# SCHEM_MOTEUR_PDB_OFA.net
KiCad netlist of a schematic drawn in Altium Designer
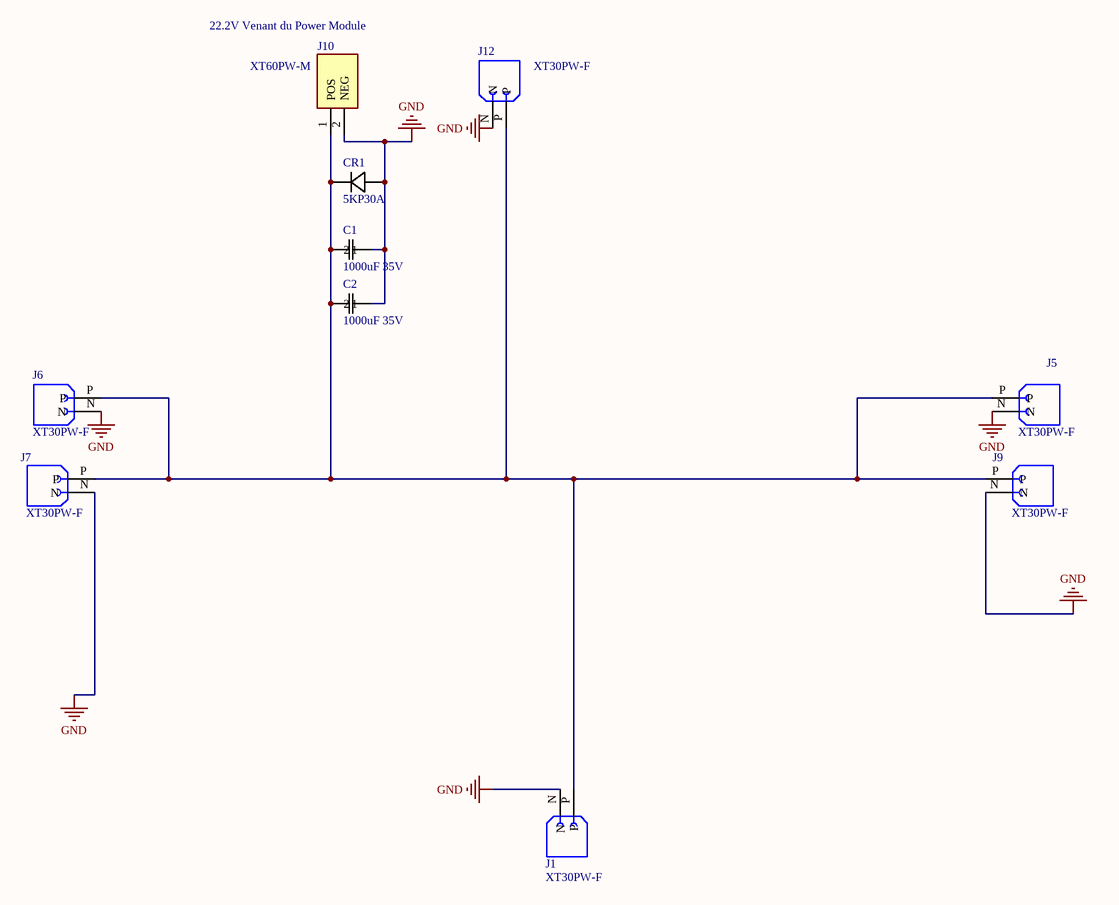
[diagram p0: SCHEM_MOTEUR_PDB_OFA.SchDoc]

(export (version "E")
  (design (tool "Eeschema 10.0.6"))
  (components
    (comp (ref "C1")
      (value "1000uF 35V")
      (footprint "CAP_RX_12P5X25_RUB")
      (fields
        (field (name "MANUFACTURER_PART_NUMBER") "35RX301000M12.5X25")
        (field (name "COPYRIGHT") "Copyright (C) 2026 Ultra Librarian. All rights reserved.")
      )
      (libsource (lib "Symbol_library") (part "35RX301000M12.5X25"))
    )
    (comp (ref "C2")
      (value "1000uF 35V")
      (footprint "CAP_RX_12P5X25_RUB")
      (fields
        (field (name "MANUFACTURER_PART_NUMBER") "35RX301000M12.5X25")
        (field (name "COPYRIGHT") "Copyright (C) 2026 Ultra Librarian. All rights reserved.")
      )
      (libsource (lib "Symbol_library") (part "35RX301000M12.5X25"))
    )
    (comp (ref "CR1")
      (value "5KP30A")
      (footprint "DIODE_P600_VIS")
      (description "Description")
      (fields (field (name "COPYRIGHT") "Copyright (C) 2026 Ultra Librarian. All rights reserved."))
      (libsource (lib "Symbol_library") (part "5KP30A"))
    )
    (comp (ref "J1")
      (value "XT30PW-F")
      (footprint "AMASS_XT30PW-F")
      (description "Socket; DC supply; XT30; female; PIN: 2; on PCBs; THT; yellow; 15A")
      (fields (field (name "MF") "amass"))
      (libsource (lib "Symbol_library") (part "XT30PW-F"))
    )
    (comp (ref "J5")
      (value "XT30PW-F")
      (footprint "AMASS_XT30PW-F")
      (description "Socket; DC supply; XT30; female; PIN: 2; on PCBs; THT; yellow; 15A")
      (fields (field (name "MF") "amass"))
      (libsource (lib "Symbol_library") (part "XT30PW-F"))
    )
    (comp (ref "J6")
      (value "XT30PW-F")
      (footprint "AMASS_XT30PW-F")
      (description "Socket; DC supply; XT30; female; PIN: 2; on PCBs; THT; yellow; 15A")
      (fields (field (name "MF") "amass"))
      (libsource (lib "") (part "XT30PW-F_1"))
    )
    (comp (ref "J7")
      (value "XT30PW-F")
      (footprint "AMASS_XT30PW-F")
      (description "Socket; DC supply; XT30; female; PIN: 2; on PCBs; THT; yellow; 15A")
      (fields (field (name "MF") "amass"))
      (libsource (lib "") (part "XT30PW-F_1"))
    )
    (comp (ref "J9")
      (value "XT30PW-F")
      (footprint "AMASS_XT30PW-F")
      (description "Socket; DC supply; XT30; female; PIN: 2; on PCBs; THT; yellow; 15A")
      (fields (field (name "MF") "amass"))
      (libsource (lib "Symbol_library") (part "XT30PW-F"))
    )
    (comp (ref "J10")
      (value "XT60PW-M")
      (footprint "AMASS_XT60PW-M")
      (description "Socket, DC supply, male, PIN: 2")
      (fields (field (name "MF") "AMASS"))
      (libsource (lib "Symbol_library") (part "XT60PW-M"))
    )
    (comp (ref "J12")
      (value "XT30PW-F")
      (footprint "AMASS_XT30PW-F")
      (description "Socket; DC supply; XT30; female; PIN: 2; on PCBs; THT; yellow; 15A")
      (fields (field (name "MF") "amass"))
      (libsource (lib "") (part "XT30PW-F_1"))
    )
  )
  (nets
    (net (code "1") (name "GND") (class "Default")
      (node (ref "C1") (pin "2") (pinfunction "2_2") (pintype "passive"))
      (node (ref "C2") (pin "2") (pinfunction "2_2") (pintype "passive"))
      (node (ref "CR1") (pin "2") (pinfunction "2_2") (pintype "passive"))
      (node (ref "J1") (pin "N") (pinfunction "N_N") (pintype "power_in"))
      (node (ref "J10") (pin "2") (pinfunction "NEG_2") (pintype "passive"))
      (node (ref "J12") (pin "N") (pinfunction "N_N") (pintype "power_in"))
      (node (ref "J5") (pin "N") (pinfunction "N_N") (pintype "power_in"))
      (node (ref "J6") (pin "N") (pinfunction "N_N") (pintype "power_in"))
      (node (ref "J7") (pin "N") (pinfunction "N_N") (pintype "power_in"))
      (node (ref "J9") (pin "N") (pinfunction "N_N") (pintype "power_in"))
    )
    (net (code "2") (name "Net-(J10-POS)") (class "Default")
      (node (ref "C1") (pin "1") (pinfunction "1_1") (pintype "passive"))
      (node (ref "C2") (pin "1") (pinfunction "1_1") (pintype "passive"))
      (node (ref "CR1") (pin "1") (pinfunction "1_1") (pintype "passive"))
      (node (ref "J1") (pin "P") (pinfunction "P_P") (pintype "power_in"))
      (node (ref "J10") (pin "1") (pinfunction "POS_1") (pintype "passive"))
      (node (ref "J12") (pin "P") (pinfunction "P_P") (pintype "power_in"))
      (node (ref "J5") (pin "P") (pinfunction "P_P") (pintype "power_in"))
      (node (ref "J6") (pin "P") (pinfunction "P_P") (pintype "power_in"))
      (node (ref "J7") (pin "P") (pinfunction "P_P") (pintype "power_in"))
      (node (ref "J9") (pin "P") (pinfunction "P_P") (pintype "power_in"))
    )
  )
)
